# USB-uart.net
KiCad netlist of a schematic drawn in Altium Designer
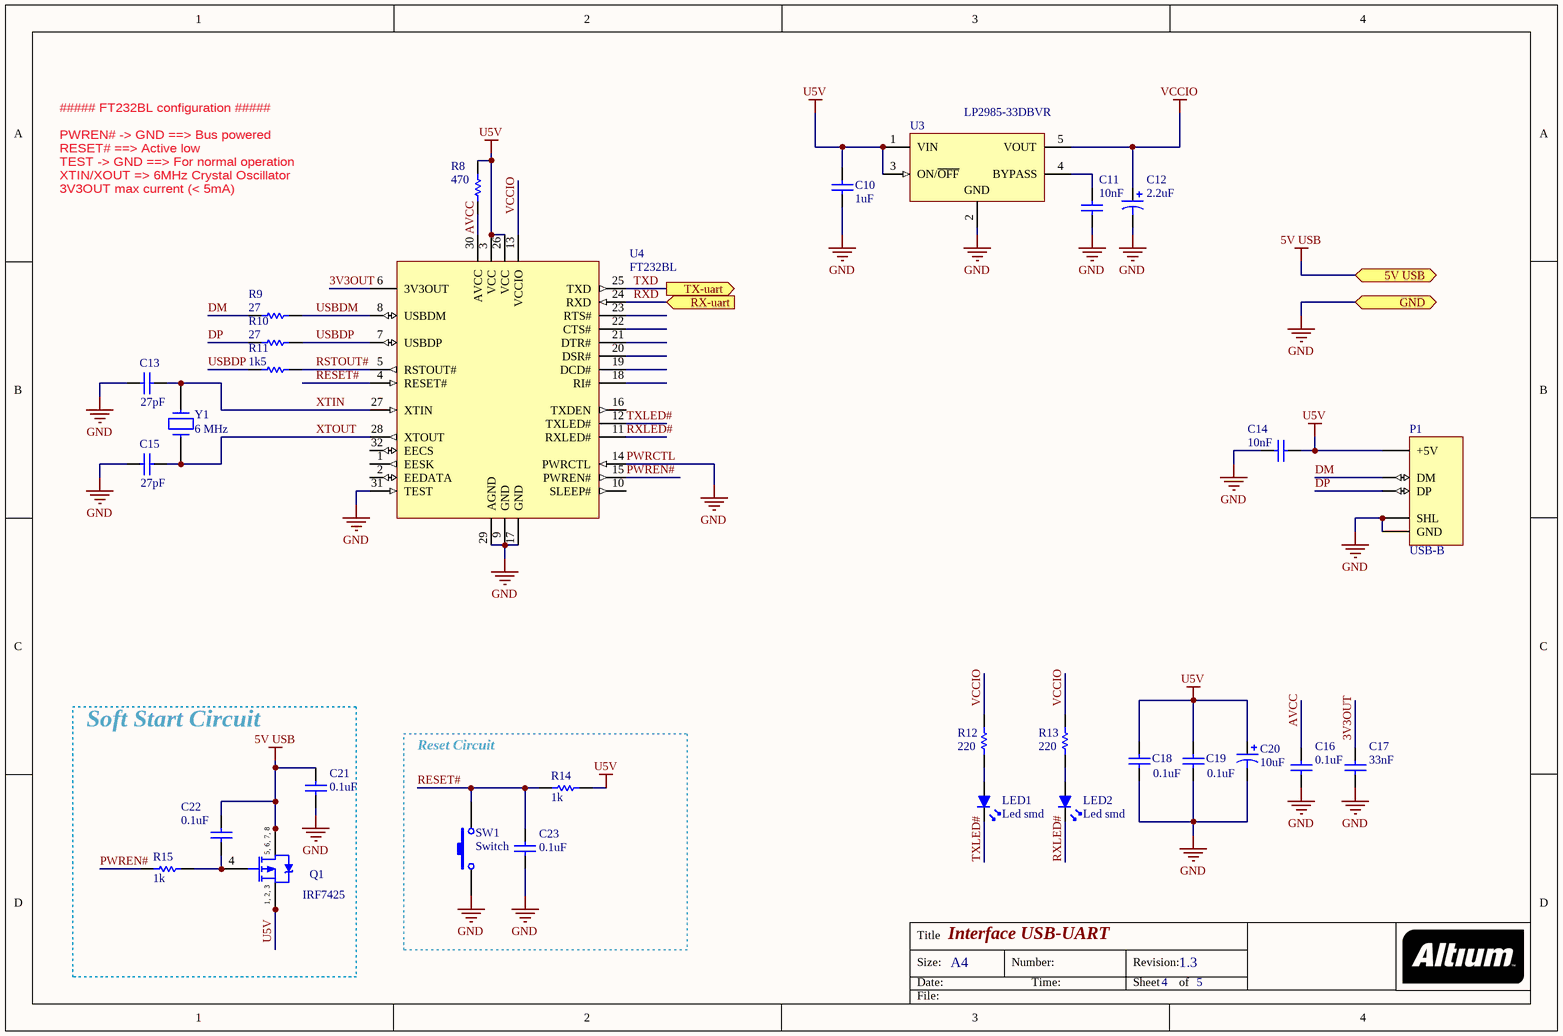
[diagram p0: USB-uart.SchDoc]

(export (version "E")
  (design (tool "Eeschema 10.0.6"))
  (components
    (comp (ref "C10")
      (value "1uF")
      (footprint "0805")
      (description "Capacitor")
      (fields (field (name "Comment") "C1u") (field (name ".CREATOR") "SR"))
      (libsource (lib "Schlib") (part "C"))
    )
    (comp (ref "C11")
      (value "10nF")
      (footprint "C 1206")
      (description "Capacitor")
      (fields (field (name "Comment") "C10n") (field (name ".CREATOR") "SR"))
      (libsource (lib "CDR_SCH") (part "C"))
    )
    (comp (ref "C12")
      (value "2.2uF")
      (footprint "Tantalum")
      (description "Tantalum capacitor")
      (fields (field (name "Comment") "CT2.2u"))
      (libsource (lib "Schlib") (part "C Tantalum"))
    )
    (comp (ref "C13")
      (value "27pF")
      (footprint "C 1206")
      (description "Capacitor")
      (fields (field (name "Comment") "C27p") (field (name ".CREATOR") "SR"))
      (libsource (lib "CDR_SCH") (part "C"))
    )
    (comp (ref "C14")
      (value "10nF")
      (footprint "C 1206")
      (description "Capacitor")
      (fields (field (name "Comment") "C10n") (field (name ".CREATOR") "SR"))
      (libsource (lib "CDR_SCH") (part "C"))
    )
    (comp (ref "C15")
      (value "27pF")
      (footprint "C 1206")
      (description "Capacitor")
      (fields (field (name "Comment") "C27p") (field (name ".CREATOR") "SR"))
      (libsource (lib "CDR_SCH") (part "C"))
    )
    (comp (ref "C16")
      (value "0.1uF")
      (footprint "C 1206")
      (description "Capacitor")
      (fields (field (name "Comment") "C0.1u") (field (name ".CREATOR") "SR"))
      (libsource (lib "CDR_SCH") (part "C"))
    )
    (comp (ref "C17")
      (value "33nF")
      (footprint "C 1206")
      (description "Capacitor")
      (fields (field (name "Comment") "C33n") (field (name ".CREATOR") "SR"))
      (libsource (lib "CDR_SCH") (part "C"))
    )
    (comp (ref "C18")
      (value "0.1uF")
      (footprint "C 1206")
      (description "Capacitor")
      (fields (field (name "Comment") "C0.1u") (field (name ".CREATOR") "SR"))
      (libsource (lib "CDR_SCH") (part "C"))
    )
    (comp (ref "C19")
      (value "0.1uF")
      (footprint "C 1206")
      (description "Capacitor")
      (fields (field (name "Comment") "C0.1u") (field (name ".CREATOR") "SR"))
      (libsource (lib "CDR_SCH") (part "C"))
    )
    (comp (ref "C20")
      (value "10uF")
      (footprint "CAP4x7x1.5mm")
      (description "Capacitor polarzado")
      (fields (field (name "Comment") "C10u"))
      (libsource (lib "Schlib") (part "Capacitor pol"))
    )
    (comp (ref "C21")
      (value "0.1uF")
      (footprint "C 1206")
      (description "Capacitor")
      (fields (field (name "Comment") "C0.1u") (field (name ".CREATOR") "SR"))
      (libsource (lib "CDR_SCH") (part "C"))
    )
    (comp (ref "C22")
      (value "0.1uF")
      (footprint "C 1206")
      (description "Capacitor")
      (fields (field (name "Comment") "C0.1u") (field (name ".CREATOR") "SR"))
      (libsource (lib "CDR_SCH") (part "C"))
    )
    (comp (ref "C23")
      (value "0.1uF")
      (footprint "C 1206")
      (description "Capacitor")
      (fields (field (name "Comment") "C0.1u") (field (name ".CREATOR") "SR"))
      (libsource (lib "CDR_SCH") (part "C"))
    )
    (comp (ref "LED1")
      (value "Led smd")
      (footprint "LED 1206")
      (description "LED red")
      (fields (field (name ".CREATOR") "SR"))
      (libsource (lib "CDR_SCH") (part "LED"))
    )
    (comp (ref "LED2")
      (value "Led smd")
      (footprint "LED 1206")
      (description "LED green")
      (fields (field (name ".CREATOR") "SR"))
      (libsource (lib "CDR_SCH") (part "LED"))
    )
    (comp (ref "P1")
      (value "USB-B")
      (footprint "USBB")
      (description "Conector USB tipo B")
      (libsource (lib "CDR_SCH") (part "USB-B"))
    )
    (comp (ref "Q1")
      (value "IRF7425")
      (footprint "SO-8_L")
      (description "HEXFET Power MOSFET")
      (fields (field (name "PUBLISHER") "Altium Limited"))
      (libsource (lib "IR Discrete MOSFET - Power") (part "IRF7425"))
    )
    (comp (ref "R8")
      (value "470")
      (footprint "R 1206")
      (description "Resistencia")
      (fields (field (name "Comment") "R470") (field (name ".CREATOR") "SR"))
      (libsource (lib "CDR_SCH") (part "R"))
    )
    (comp (ref "R9")
      (value "27")
      (footprint "R 1206")
      (description "Resistencia")
      (fields (field (name "Comment") "R27") (field (name ".CREATOR") "SR"))
      (libsource (lib "CDR_SCH") (part "R"))
    )
    (comp (ref "R10")
      (value "27")
      (footprint "R 1206")
      (description "Resistencia")
      (fields (field (name "Comment") "R27") (field (name ".CREATOR") "SR"))
      (libsource (lib "CDR_SCH") (part "R"))
    )
    (comp (ref "R11")
      (value "1k5")
      (footprint "R 1206")
      (description "Resistencia")
      (fields (field (name "Comment") "R1k5") (field (name ".CREATOR") "SR"))
      (libsource (lib "CDR_SCH") (part "R"))
    )
    (comp (ref "R12")
      (value "220")
      (footprint "R 1206")
      (description "Resistencia")
      (fields (field (name "Comment") "R220") (field (name ".CREATOR") "SR"))
      (libsource (lib "CDR_SCH") (part "R"))
    )
    (comp (ref "R13")
      (value "220")
      (footprint "R 1206")
      (description "Resistencia")
      (fields (field (name "Comment") "R220") (field (name ".CREATOR") "SR"))
      (libsource (lib "CDR_SCH") (part "R"))
    )
    (comp (ref "R14")
      (value "1k")
      (footprint "R 1206")
      (description "Resistencia")
      (fields (field (name "Comment") "R1k") (field (name ".CREATOR") "SR"))
      (libsource (lib "CDR_SCH") (part "R"))
    )
    (comp (ref "R15")
      (value "1k")
      (footprint "R 1206")
      (description "Resistencia")
      (fields (field (name "Comment") "R1k") (field (name ".CREATOR") "SR"))
      (libsource (lib "CDR_SCH") (part "R"))
    )
    (comp (ref "SW1")
      (value "Switch")
      (footprint "TACT SW")
      (fields (field (name ".CREATOR") "G") (field (name ".PCBCHECK") "G") (field (name ".SCHCHECK") "G"))
      (libsource (lib "CDR_SCH") (part "Pulsador NA 4 term"))
    )
    (comp (ref "U3")
      (value "LP2985-33DBVR")
      (footprint "TI-DBV5_N")
      (fields (field (name "MANUFACTURER") "Texas Instruments"))
      (libsource (lib "TI Power Management Linear Regulator Single Channel LDO (0-350mA)") (part "LP2985-10DBVR"))
    )
    (comp (ref "U4")
      (value "FT232BL")
      (footprint "LQFP-32_N")
      (description "USB UART Asynchronous Serial Data Transfer Chip, LQFP-32, Pb-Free")
      (fields (field (name "PUBLISHER") "Altium Limited"))
      (libsource (lib "FTDI Communication UART") (part "FT232BL"))
    )
    (comp (ref "Y1")
      (value "6 MHz")
      (footprint "Y TRHU")
      (description "Cristal de 6Mhz")
      (fields (field (name "Comment") "Cristal de Cuarzo") (field (name ".CREATOR") "G"))
      (libsource (lib "CDR_SCH") (part "Cristal de Cuarzo"))
    )
  )
  (nets
    (net (code "1") (name "/3V3OUT") (class "Default")
      (node (ref "C17") (pin "2") (pinfunction "2_2") (pintype "passive"))
      (node (ref "U4") (pin "6") (pinfunction "3V3OUT_6") (pintype "power_in"))
    )
    (net (code "2") (name "/AVCC") (class "Default")
      (node (ref "C16") (pin "2") (pinfunction "2_2") (pintype "passive"))
      (node (ref "R8") (pin "2") (pinfunction "2_2") (pintype "passive"))
      (node (ref "U4") (pin "30") (pinfunction "AVCC_30") (pintype "power_in"))
    )
    (net (code "3") (name "/DM") (class "Default")
      (node (ref "P1") (pin "2") (pinfunction "DM_2") (pintype "bidirectional"))
      (node (ref "R9") (pin "2") (pinfunction "2_2") (pintype "passive"))
    )
    (net (code "4") (name "/DP") (class "Default")
      (node (ref "P1") (pin "3") (pinfunction "DP_3") (pintype "bidirectional"))
      (node (ref "R10") (pin "2") (pinfunction "2_2") (pintype "passive"))
    )
    (net (code "5") (name "/PWREN#") (class "Default")
      (node (ref "R15") (pin "1") (pinfunction "1_1") (pintype "passive"))
      (node (ref "U4") (pin "15") (pinfunction "PWREN#_15") (pintype "output"))
    )
    (net (code "6") (name "/RESET#") (class "Default")
      (node (ref "C23") (pin "1") (pinfunction "1_1") (pintype "passive"))
      (node (ref "R14") (pin "1") (pinfunction "1_1") (pintype "passive"))
      (node (ref "SW1") (pin "2") (pinfunction "2_2") (pintype "passive"))
      (node (ref "U4") (pin "4") (pinfunction "RESET#_4") (pintype "input"))
    )
    (net (code "7") (name "/RSTOUT#") (class "Default")
      (node (ref "R11") (pin "1") (pinfunction "1_1") (pintype "passive"))
      (node (ref "U4") (pin "5") (pinfunction "RSTOUT#_5") (pintype "output"))
    )
    (net (code "8") (name "/RXD") (class "Default")
      (node (ref "U4") (pin "24") (pinfunction "RXD_24") (pintype "input"))
    )
    (net (code "9") (name "/RXLED#") (class "Default")
      (node (ref "LED2") (pin "2") (pinfunction "K_2") (pintype "passive"))
      (node (ref "U4") (pin "11") (pinfunction "RXLED#_11") (pintype "open_collector"))
    )
    (net (code "10") (name "/TXD") (class "Default")
      (node (ref "U4") (pin "25") (pinfunction "TXD_25") (pintype "output"))
    )
    (net (code "11") (name "/TXLED#") (class "Default")
      (node (ref "LED1") (pin "2") (pinfunction "K_2") (pintype "passive"))
      (node (ref "U4") (pin "12") (pinfunction "TXLED#_12") (pintype "open_collector"))
    )
    (net (code "12") (name "/USBDM") (class "Default")
      (node (ref "R9") (pin "1") (pinfunction "1_1") (pintype "passive"))
      (node (ref "U4") (pin "8") (pinfunction "USBDM_8") (pintype "bidirectional"))
    )
    (net (code "13") (name "/USBDP") (class "Default")
      (node (ref "R10") (pin "1") (pinfunction "1_1") (pintype "passive"))
      (node (ref "R11") (pin "2") (pinfunction "2_2") (pintype "passive"))
      (node (ref "U4") (pin "7") (pinfunction "USBDP_7") (pintype "bidirectional"))
    )
    (net (code "14") (name "/XTIN") (class "Default")
      (node (ref "C13") (pin "1") (pinfunction "1_1") (pintype "passive"))
      (node (ref "U4") (pin "27") (pinfunction "XTIN_27") (pintype "input"))
      (node (ref "Y1") (pin "1") (pinfunction "1_1") (pintype "power_in"))
    )
    (net (code "15") (name "/XTOUT") (class "Default")
      (node (ref "C15") (pin "1") (pinfunction "1_1") (pintype "passive"))
      (node (ref "U4") (pin "28") (pinfunction "XTOUT_28") (pintype "output"))
      (node (ref "Y1") (pin "2") (pinfunction "2_2") (pintype "passive"))
    )
    (net (code "16") (name "5V USB") (class "Default")
      (node (ref "C21") (pin "1") (pinfunction "1_1") (pintype "passive"))
      (node (ref "C22") (pin "1") (pinfunction "1_1") (pintype "passive"))
      (node (ref "Q1") (pin "5") (pinfunction "D_5") (pintype "passive"))
      (node (ref "Q1") (pin "6") (pinfunction "D_6") (pintype "passive"))
      (node (ref "Q1") (pin "7") (pinfunction "D_7") (pintype "passive"))
      (node (ref "Q1") (pin "8") (pinfunction "D_8") (pintype "passive"))
    )
    (net (code "17") (name "GND") (class "Default")
      (node (ref "C10") (pin "2") (pinfunction "2_2") (pintype "passive"))
      (node (ref "C11") (pin "2") (pinfunction "2_2") (pintype "passive"))
      (node (ref "C12") (pin "2") (pinfunction "2_2") (pintype "passive"))
      (node (ref "C13") (pin "2") (pinfunction "2_2") (pintype "passive"))
      (node (ref "C14") (pin "2") (pinfunction "2_2") (pintype "passive"))
      (node (ref "C15") (pin "2") (pinfunction "2_2") (pintype "passive"))
      (node (ref "C16") (pin "1") (pinfunction "1_1") (pintype "passive"))
      (node (ref "C17") (pin "1") (pinfunction "1_1") (pintype "passive"))
      (node (ref "C18") (pin "1") (pinfunction "1_1") (pintype "passive"))
      (node (ref "C19") (pin "1") (pinfunction "1_1") (pintype "passive"))
      (node (ref "C20") (pin "2") (pinfunction "2_2") (pintype "passive"))
      (node (ref "C21") (pin "2") (pinfunction "2_2") (pintype "passive"))
      (node (ref "C23") (pin "2") (pinfunction "2_2") (pintype "passive"))
      (node (ref "P1") (pin "0") (pinfunction "SHL_0") (pintype "passive"))
      (node (ref "P1") (pin "4") (pinfunction "GND_4") (pintype "power_in"))
      (node (ref "SW1") (pin "1") (pinfunction "1_1") (pintype "passive"))
      (node (ref "U3") (pin "2") (pinfunction "GND_2") (pintype "power_in"))
      (node (ref "U4") (pin "14") (pinfunction "PWRCTL_14") (pintype "input"))
      (node (ref "U4") (pin "17") (pinfunction "GND_17") (pintype "power_in"))
      (node (ref "U4") (pin "29") (pinfunction "AGND_29") (pintype "power_in"))
      (node (ref "U4") (pin "31") (pinfunction "TEST_31") (pintype "input"))
      (node (ref "U4") (pin "9") (pinfunction "GND_9") (pintype "power_in"))
    )
    (net (code "18") (name "Net-(LED1-A)") (class "Default")
      (node (ref "LED1") (pin "1") (pinfunction "A_1") (pintype "passive"))
      (node (ref "R12") (pin "2") (pinfunction "2_2") (pintype "passive"))
    )
    (net (code "19") (name "Net-(LED2-A)") (class "Default")
      (node (ref "LED2") (pin "1") (pinfunction "A_1") (pintype "passive"))
      (node (ref "R13") (pin "2") (pinfunction "2_2") (pintype "passive"))
    )
    (net (code "20") (name "Net-(Q1-G)") (class "Default")
      (node (ref "C22") (pin "2") (pinfunction "2_2") (pintype "passive"))
      (node (ref "Q1") (pin "4") (pinfunction "G_4") (pintype "passive"))
      (node (ref "R15") (pin "2") (pinfunction "2_2") (pintype "passive"))
    )
    (net (code "21") (name "Net-(U3-BYPASS)") (class "Default")
      (node (ref "C11") (pin "1") (pinfunction "1_1") (pintype "passive"))
      (node (ref "U3") (pin "4") (pinfunction "BYPASS_4") (pintype "passive"))
    )
    (net (code "22") (name "U5V") (class "Default")
      (node (ref "C10") (pin "1") (pinfunction "1_1") (pintype "passive"))
      (node (ref "C14") (pin "1") (pinfunction "1_1") (pintype "passive"))
      (node (ref "C18") (pin "2") (pinfunction "2_2") (pintype "passive"))
      (node (ref "C19") (pin "2") (pinfunction "2_2") (pintype "passive"))
      (node (ref "C20") (pin "1") (pinfunction "1_1") (pintype "passive"))
      (node (ref "P1") (pin "1") (pinfunction "+5V_1") (pintype "power_in"))
      (node (ref "Q1") (pin "1") (pinfunction "S_1") (pintype "passive"))
      (node (ref "Q1") (pin "2") (pinfunction "S_2") (pintype "passive"))
      (node (ref "Q1") (pin "3") (pinfunction "S_3") (pintype "passive"))
      (node (ref "R14") (pin "2") (pinfunction "2_2") (pintype "passive"))
      (node (ref "R8") (pin "1") (pinfunction "1_1") (pintype "passive"))
      (node (ref "U3") (pin "1") (pinfunction "VIN_1") (pintype "power_in"))
      (node (ref "U3") (pin "3") (pinfunction "ON/~{OFF}_3") (pintype "input"))
      (node (ref "U4") (pin "26") (pinfunction "VCC_26") (pintype "power_in"))
      (node (ref "U4") (pin "3") (pinfunction "VCC_3") (pintype "power_in"))
    )
    (net (code "23") (name "VCCIO") (class "Default")
      (node (ref "C12") (pin "1") (pinfunction "1_1") (pintype "passive"))
      (node (ref "R12") (pin "1") (pinfunction "1_1") (pintype "passive"))
      (node (ref "R13") (pin "1") (pinfunction "1_1") (pintype "passive"))
      (node (ref "U3") (pin "5") (pinfunction "VOUT_5") (pintype "power_in"))
      (node (ref "U4") (pin "13") (pinfunction "VCCIO_13") (pintype "power_in"))
    )
    (net (code "24") (name "unconnected-(U4-CTS#-Pad22)") (class "Default")
      (node (ref "U4") (pin "22") (pinfunction "CTS#_22") (pintype "tri_state"))
    )
    (net (code "25") (name "unconnected-(U4-DCD#-Pad19)") (class "Default")
      (node (ref "U4") (pin "19") (pinfunction "DCD#_19") (pintype "tri_state"))
    )
    (net (code "26") (name "unconnected-(U4-DSR#-Pad20)") (class "Default")
      (node (ref "U4") (pin "20") (pinfunction "DSR#_20") (pintype "tri_state"))
    )
    (net (code "27") (name "unconnected-(U4-DTR#-Pad21)") (class "Default")
      (node (ref "U4") (pin "21") (pinfunction "DTR#_21") (pintype "tri_state"))
    )
    (net (code "28") (name "unconnected-(U4-EECS-Pad32)") (class "Default")
      (node (ref "U4") (pin "32") (pinfunction "EECS_32") (pintype "bidirectional"))
    )
    (net (code "29") (name "unconnected-(U4-EEDATA-Pad2)") (class "Default")
      (node (ref "U4") (pin "2") (pinfunction "EEDATA_2") (pintype "bidirectional"))
    )
    (net (code "30") (name "unconnected-(U4-EESK-Pad1)") (class "Default")
      (node (ref "U4") (pin "1") (pinfunction "EESK_1") (pintype "output"))
    )
    (net (code "31") (name "unconnected-(U4-RI#-Pad18)") (class "Default")
      (node (ref "U4") (pin "18") (pinfunction "RI#_18") (pintype "tri_state"))
    )
    (net (code "32") (name "unconnected-(U4-RTS#-Pad23)") (class "Default")
      (node (ref "U4") (pin "23") (pinfunction "RTS#_23") (pintype "tri_state"))
    )
    (net (code "33") (name "unconnected-(U4-SLEEP#-Pad10)") (class "Default")
      (node (ref "U4") (pin "10") (pinfunction "SLEEP#_10") (pintype "output"))
    )
    (net (code "34") (name "unconnected-(U4-TXDEN-Pad16)") (class "Default")
      (node (ref "U4") (pin "16") (pinfunction "TXDEN_16") (pintype "output"))
    )
  )
)
